# igrid_sensor.net
KiCad netlist of a schematic drawn in Altium Designer
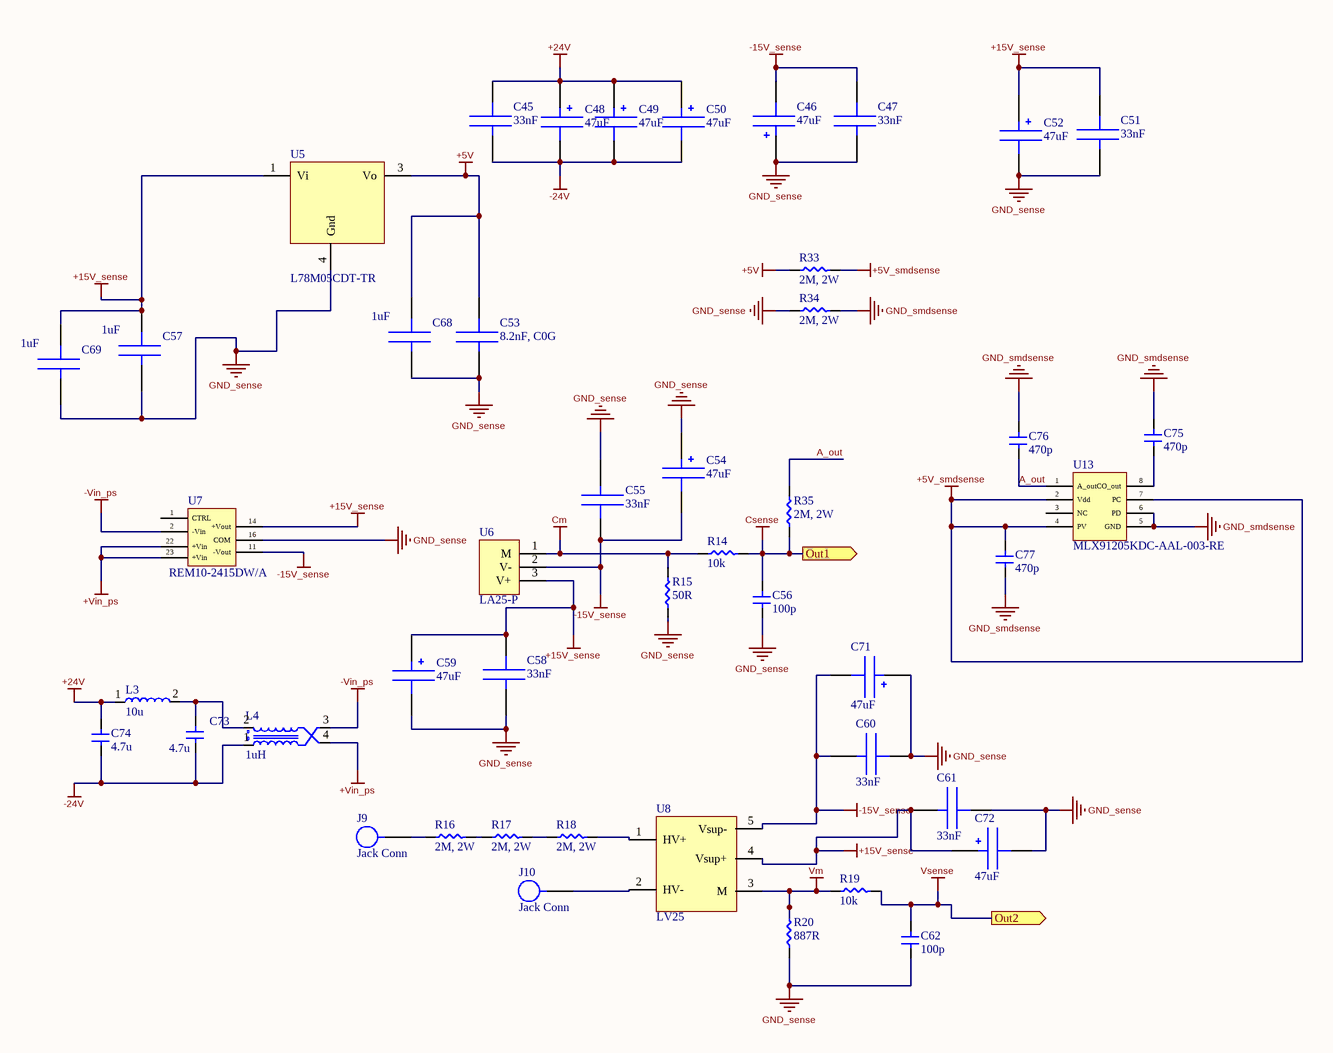
[diagram p0: igrid_sensor.SchDoc]

(export (version "E")
  (design (tool "Eeschema 10.0.6"))
  (components
    (comp (ref "C45")
      (value "33nF")
      (footprint "C1206")
      (description "Cap Ceramic 0.033uF 50V X7R 5% SMD 1206 125C Paper T/R")
      (fields
        (field (name "MANUFACTURER") "Samsung")
        (field (name "MANUFACTURER PART NUMBER") "CL31B333JBCNNNC")
      )
      (libsource (lib "power_ckt") (part "CL31B333JBCNNNC"))
    )
    (comp (ref "C46")
      (value "47uF")
      (footprint "CAPAE7266X82N")
      (description "Aluminum Electrolytic Capacitors - SMD 47uF 50V 105c")
      (fields
        (field (name "MANUFACTURER") "Nichicon")
        (field (name "MANUFACTURER PART NUMBER") "UCD1H470MCL1GS")
      )
      (libsource (lib "power_ckt") (part "UCD1H470MCL1GS"))
    )
    (comp (ref "C47")
      (value "33nF")
      (footprint "C1206")
      (description "Cap Ceramic 0.033uF 50V X7R 5% SMD 1206 125C Paper T/R")
      (fields
        (field (name "MANUFACTURER") "Samsung")
        (field (name "MANUFACTURER PART NUMBER") "CL31B333JBCNNNC")
      )
      (libsource (lib "power_ckt") (part "CL31B333JBCNNNC"))
    )
    (comp (ref "C48")
      (value "47uF")
      (footprint "CAPAE7266X82N")
      (description "Aluminum Electrolytic Capacitors - SMD 47uF 50V 105c")
      (fields
        (field (name "MANUFACTURER") "Nichicon")
        (field (name "MANUFACTURER PART NUMBER") "UCD1H470MCL1GS")
      )
      (libsource (lib "power_ckt") (part "UCD1H470MCL1GS"))
    )
    (comp (ref "C49")
      (value "47uF")
      (footprint "CAPAE7266X82N")
      (description "Aluminum Electrolytic Capacitors - SMD 47uF 50V 105c")
      (fields
        (field (name "MANUFACTURER") "Nichicon")
        (field (name "MANUFACTURER PART NUMBER") "UCD1H470MCL1GS")
      )
      (libsource (lib "power_ckt") (part "UCD1H470MCL1GS"))
    )
    (comp (ref "C50")
      (value "47uF")
      (footprint "CAPAE7266X82N")
      (description "Aluminum Electrolytic Capacitors - SMD 47uF 50V 105c")
      (fields
        (field (name "MANUFACTURER") "Nichicon")
        (field (name "MANUFACTURER PART NUMBER") "UCD1H470MCL1GS")
      )
      (libsource (lib "power_ckt") (part "UCD1H470MCL1GS"))
    )
    (comp (ref "C51")
      (value "33nF")
      (footprint "C1206")
      (description "Cap Ceramic 0.033uF 50V X7R 5% SMD 1206 125C Paper T/R")
      (fields
        (field (name "MANUFACTURER") "Samsung")
        (field (name "MANUFACTURER PART NUMBER") "CL31B333JBCNNNC")
      )
      (libsource (lib "power_ckt") (part "CL31B333JBCNNNC"))
    )
    (comp (ref "C52")
      (value "47uF")
      (footprint "CAPAE7266X82N")
      (description "Aluminum Electrolytic Capacitors - SMD 47uF 50V 105c")
      (fields
        (field (name "MANUFACTURER") "Nichicon")
        (field (name "MANUFACTURER PART NUMBER") "UCD1H470MCL1GS")
      )
      (libsource (lib "power_ckt") (part "UCD1H470MCL1GS"))
    )
    (comp (ref "C53")
      (value "8.2nF, C0G")
      (footprint "C1206")
      (description "Multilayer Ceramic Capacitors MLCC - SMD/SMT 250volts 8200pF 5% C0G AUTO")
      (fields
        (field (name "MANUFACTURER") "KEMET")
        (field (name "MANUFACTURER PART NUMBER") "C1206C822JAGACAUTO")
      )
      (libsource (lib "power_ckt") (part "C1206C822JAGACAUTO"))
    )
    (comp (ref "C54")
      (value "47uF")
      (footprint "CAPAE7266X82N")
      (description "Aluminum Electrolytic Capacitors - SMD 47uF 50V 105c")
      (fields
        (field (name "MANUFACTURER") "Nichicon")
        (field (name "MANUFACTURER PART NUMBER") "UCD1H470MCL1GS")
      )
      (libsource (lib "power_ckt") (part "UCD1H470MCL1GS"))
    )
    (comp (ref "C55")
      (value "33nF")
      (footprint "C1206")
      (description "Cap Ceramic 0.033uF 50V X7R 5% SMD 1206 125C Paper T/R")
      (fields
        (field (name "MANUFACTURER") "Samsung")
        (field (name "MANUFACTURER PART NUMBER") "CL31B333JBCNNNC")
      )
      (libsource (lib "power_ckt") (part "CL31B333JBCNNNC"))
    )
    (comp (ref "C56")
      (value "100p")
      (footprint "C0603")
      (description "Cap Ceramic 100pF 50V X7R 10% SMD 0603 125C T/R")
      (fields
        (field (name "MANUFACTURER") "Kyocera AVX")
        (field (name "MANUFACTURER PART NUMBER") "06035C101KAT2A")
      )
      (libsource (lib "voltage_sense") (part "06035C101KAT2A"))
    )
    (comp (ref "C57")
      (value "1uF")
      (footprint "C1206")
      (description "Multilayer Ceramic Capacitors MLCC - SMD/SMT 250volts 8200pF 5% C0G AUTO")
      (fields
        (field (name "MANUFACTURER") "KEMET")
        (field (name "MANUFACTURER PART NUMBER") "C1206C822JAGACAUTO")
      )
      (libsource (lib "power_ckt") (part "C1206C822JAGACAUTO"))
    )
    (comp (ref "C58")
      (value "33nF")
      (footprint "C1206")
      (description "Cap Ceramic 0.033uF 50V X7R 5% SMD 1206 125C Paper T/R")
      (fields
        (field (name "MANUFACTURER") "Samsung")
        (field (name "MANUFACTURER PART NUMBER") "CL31B333JBCNNNC")
      )
      (libsource (lib "power_ckt") (part "CL31B333JBCNNNC"))
    )
    (comp (ref "C59")
      (value "47uF")
      (footprint "CAPAE7266X82N")
      (description "Aluminum Electrolytic Capacitors - SMD 47uF 50V 105c")
      (fields
        (field (name "MANUFACTURER") "Nichicon")
        (field (name "MANUFACTURER PART NUMBER") "UCD1H470MCL1GS")
      )
      (libsource (lib "power_ckt") (part "UCD1H470MCL1GS"))
    )
    (comp (ref "C60")
      (value "33nF")
      (footprint "C1206")
      (description "Cap Ceramic 0.033uF 50V X7R 5% SMD 1206 125C Paper T/R")
      (fields
        (field (name "MANUFACTURER") "Samsung")
        (field (name "MANUFACTURER PART NUMBER") "CL31B333JBCNNNC")
      )
      (libsource (lib "power_ckt") (part "CL31B333JBCNNNC"))
    )
    (comp (ref "C61")
      (value "33nF")
      (footprint "C1206")
      (description "Cap Ceramic 0.033uF 50V X7R 5% SMD 1206 125C Paper T/R")
      (fields
        (field (name "MANUFACTURER") "Samsung")
        (field (name "MANUFACTURER PART NUMBER") "CL31B333JBCNNNC")
      )
      (libsource (lib "power_ckt") (part "CL31B333JBCNNNC"))
    )
    (comp (ref "C62")
      (value "100p")
      (footprint "C0603")
      (description "Cap Ceramic 100pF 50V X7R 10% SMD 0603 125C T/R")
      (fields
        (field (name "MANUFACTURER") "Kyocera AVX")
        (field (name "MANUFACTURER PART NUMBER") "06035C101KAT2A")
      )
      (libsource (lib "voltage_sense") (part "06035C101KAT2A"))
    )
    (comp (ref "C68")
      (value "1uF")
      (footprint "C1206")
      (description "Multilayer Ceramic Capacitors MLCC - SMD/SMT 250volts 8200pF 5% C0G AUTO")
      (fields
        (field (name "MANUFACTURER") "KEMET")
        (field (name "MANUFACTURER PART NUMBER") "C1206C822JAGACAUTO")
      )
      (libsource (lib "power_ckt") (part "C1206C822JAGACAUTO"))
    )
    (comp (ref "C69")
      (value "1uF")
      (footprint "C1206")
      (description "Multilayer Ceramic Capacitors MLCC - SMD/SMT 250volts 8200pF 5% C0G AUTO")
      (fields
        (field (name "MANUFACTURER") "KEMET")
        (field (name "MANUFACTURER PART NUMBER") "C1206C822JAGACAUTO")
      )
      (libsource (lib "power_ckt") (part "C1206C822JAGACAUTO"))
    )
    (comp (ref "C71")
      (value "47uF")
      (footprint "CAPAE7266X82N")
      (description "Aluminum Electrolytic Capacitors - SMD 47uF 50V 105c")
      (fields
        (field (name "MANUFACTURER") "Nichicon")
        (field (name "MANUFACTURER PART NUMBER") "UCD1H470MCL1GS")
      )
      (libsource (lib "power_ckt") (part "UCD1H470MCL1GS"))
    )
    (comp (ref "C72")
      (value "47uF")
      (footprint "CAPAE7266X82N")
      (description "Aluminum Electrolytic Capacitors - SMD 47uF 50V 105c")
      (fields
        (field (name "MANUFACTURER") "Nichicon")
        (field (name "MANUFACTURER PART NUMBER") "UCD1H470MCL1GS")
      )
      (libsource (lib "power_ckt") (part "UCD1H470MCL1GS"))
    )
    (comp (ref "C73")
      (value "4.7u")
      (footprint "C0805")
      (description "CAP CER 10000PF 50V C0G 0805")
      (fields
        (field (name "MANUFACTURER") "TDK")
        (field (name "MANUFACTURER PART NUMBER") "CGA4C2C0G1H103J060AA")
      )
      (libsource (lib "24_12_buck") (part "CGA4C2C0G1H103J060AA"))
    )
    (comp (ref "C74")
      (value "4.7u")
      (footprint "C0805")
      (description "CAP CER 10000PF 50V C0G 0805")
      (fields
        (field (name "MANUFACTURER") "TDK")
        (field (name "MANUFACTURER PART NUMBER") "CGA4C2C0G1H103J060AA")
      )
      (libsource (lib "24_12_buck") (part "CGA4C2C0G1H103J060AA"))
    )
    (comp (ref "C75")
      (value "470p")
      (footprint "C0603")
      (fields
        (field (name "MANUFACTURER") "Yageo")
        (field (name "MANUFACTURER PART NUMBER") "CC0603KRX7R9BB471")
        (field (name "TOLERANCE") "10%")
      )
      (libsource (lib "current_sense") (part "CC0603KRX7R9BB471"))
    )
    (comp (ref "C76")
      (value "470p")
      (footprint "C0603")
      (fields
        (field (name "MANUFACTURER") "Yageo")
        (field (name "MANUFACTURER PART NUMBER") "CC0603KRX7R9BB471")
        (field (name "TOLERANCE") "10%")
      )
      (libsource (lib "current_sense") (part "CC0603KRX7R9BB471"))
    )
    (comp (ref "C77")
      (value "470p")
      (footprint "C0603")
      (fields
        (field (name "MANUFACTURER") "Yageo")
        (field (name "MANUFACTURER PART NUMBER") "CC0603KRX7R9BB471")
        (field (name "TOLERANCE") "10%")
      )
      (libsource (lib "current_sense") (part "CC0603KRX7R9BB471"))
    )
    (comp (ref "J9")
      (value "Jack Conn")
      (footprint "575-4")
      (description "JACK NON-INSULATED .218\"")
      (fields
        (field (name "MANUFACTURER") "Keystone Electronics")
        (field (name "MANUFACTURER PART NUMBER") "575-4")
      )
      (libsource (lib "current_sense") (part "575-4"))
    )
    (comp (ref "J10")
      (value "Jack Conn")
      (footprint "575-4")
      (description "JACK NON-INSULATED .218\"")
      (fields
        (field (name "MANUFACTURER") "Keystone Electronics")
        (field (name "MANUFACTURER PART NUMBER") "575-4")
      )
      (libsource (lib "current_sense") (part "575-4"))
    )
    (comp (ref "L3")
      (value "10u")
      (footprint "SRP4020TA-100M")
      (description "Ind Power Shielded Wirewound 10uH 20% 100KHz Carbonyl Powder 1.8A T/R")
      (fields
        (field (name "MANUFACTURER") "Bourns")
        (field (name "MANUFACTURER PART NUMBER") "SRP4020TA-100M")
      )
      (libsource (lib "24_12_buck") (part "SRP4020TA-100M"))
    )
    (comp (ref "L4")
      (value "1uH")
      (footprint "744282010")
      (description "CHOKE COM MODE 2 X 1.0UH 4.75A")
      (fields
        (field (name "MANUFACTURER") "Wurth Electronics")
        (field (name "MANUFACTURER PART NUMBER") "744282010")
      )
      (libsource (lib "current_sense") (part "744282010"))
    )
    (comp (ref "R14")
      (value "10k")
      (footprint "R0603")
      (description "RES 10K OHM 1% 1/8W 0603")
      (fields
        (field (name "MANUFACTURER") "Stackpole Electronics")
        (field (name "MANUFACTURER PART NUMBER") "RNCP0603FTD10K0")
      )
      (libsource (lib "voltage_sense") (part "RNCP0603FTD10K0"))
    )
    (comp (ref "R15")
      (value "50R")
      (footprint "R0603")
      (fields
        (field (name "MANUFACTURER") "Panasonic")
        (field (name "MANUFACTURER PART NUMBER") "ERA3AEB7320V")
        (field (name "TOLERANCE") "0.1%")
      )
      (libsource (lib "24_12_buck") (part "ERA3AEB7320V"))
    )
    (comp (ref "R16")
      (value "2M, 2W")
      (footprint "R2010")
      (description "Supplied as a Tape, 2MΩ 2010 Thick Film SMD Resistor ±1% 2W - 35022M0FT")
      (fields
        (field (name "MANUFACTURER") "TE Connectivity")
        (field (name "MANUFACTURER PART NUMBER") "35022M0FT")
      )
      (libsource (lib "voltage_sense") (part "35022M0FT"))
    )
    (comp (ref "R17")
      (value "2M, 2W")
      (footprint "R2010")
      (description "Supplied as a Tape, 2MΩ 2010 Thick Film SMD Resistor ±1% 2W - 35022M0FT")
      (fields
        (field (name "MANUFACTURER") "TE Connectivity")
        (field (name "MANUFACTURER PART NUMBER") "35022M0FT")
      )
      (libsource (lib "voltage_sense") (part "35022M0FT"))
    )
    (comp (ref "R18")
      (value "2M, 2W")
      (footprint "R2010")
      (description "Supplied as a Tape, 2MΩ 2010 Thick Film SMD Resistor ±1% 2W - 35022M0FT")
      (fields
        (field (name "MANUFACTURER") "TE Connectivity")
        (field (name "MANUFACTURER PART NUMBER") "35022M0FT")
      )
      (libsource (lib "voltage_sense") (part "35022M0FT"))
    )
    (comp (ref "R19")
      (value "10k")
      (footprint "R0603")
      (description "RES 10K OHM 1% 1/8W 0603")
      (fields
        (field (name "MANUFACTURER") "Stackpole Electronics")
        (field (name "MANUFACTURER PART NUMBER") "RNCP0603FTD10K0")
      )
      (libsource (lib "voltage_sense") (part "RNCP0603FTD10K0"))
    )
    (comp (ref "R20")
      (value "887R")
      (footprint "R0603")
      (description "RES SMD 887 OHM 0.1% 1/10W 0603")
      (fields
        (field (name "MANUFACTURER") "Panasonic")
        (field (name "MANUFACTURER PART NUMBER") "ERA-3AEB8870V")
      )
      (libsource (lib "voltage_sense") (part "ERA-3AEB8870V"))
    )
    (comp (ref "R33")
      (value "2M, 2W")
      (footprint "R2010")
      (description "Supplied as a Tape, 2MΩ 2010 Thick Film SMD Resistor ±1% 2W - 35022M0FT")
      (fields
        (field (name "MANUFACTURER") "TE Connectivity")
        (field (name "MANUFACTURER PART NUMBER") "35022M0FT")
      )
      (libsource (lib "voltage_sense") (part "35022M0FT"))
    )
    (comp (ref "R34")
      (value "2M, 2W")
      (footprint "R2010")
      (description "Supplied as a Tape, 2MΩ 2010 Thick Film SMD Resistor ±1% 2W - 35022M0FT")
      (fields
        (field (name "MANUFACTURER") "TE Connectivity")
        (field (name "MANUFACTURER PART NUMBER") "35022M0FT")
      )
      (libsource (lib "voltage_sense") (part "35022M0FT"))
    )
    (comp (ref "R35")
      (value "2M, 2W")
      (footprint "R2010")
      (description "Supplied as a Tape, 2MΩ 2010 Thick Film SMD Resistor ±1% 2W - 35022M0FT")
      (fields
        (field (name "MANUFACTURER") "TE Connectivity")
        (field (name "MANUFACTURER PART NUMBER") "35022M0FT")
      )
      (libsource (lib "voltage_sense") (part "35022M0FT"))
    )
    (comp (ref "U5")
      (value "L78M05CDT-TR")
      (footprint "DPAK_LM7805")
      (description "STMICROELECTRONICS   L78M05CDT-TR   LINEAR VOLTAGE REGULATOR, 5V, DPAK-3")
      (fields (field (name "MANUFACTURER") "STMicroelectronics") (field (name "TOLERANCE") "5%"))
      (libsource (lib "24_12_buck") (part "L78M05CDT-TR"))
    )
    (comp (ref "U6")
      (value "LA25-P")
      (footprint "LA 25-P")
      (fields (field (name "MANUFACTURER") "LEM"))
      (libsource (lib "current_sense") (part "LA25-P"))
    )
    (comp (ref "U7")
      (value "REM10-2415DW/A")
      (footprint "REM10-2415DW/A")
      (description "Isolated DC/DC Converters 10W 9-36Vin +/-15Vout DIP24")
      (fields (field (name "MANUFACTURER") "Recom"))
      (libsource (lib "current_sense") (part "REM10-2415DW/A"))
    )
    (comp (ref "U8")
      (value "LV25")
      (footprint "LV25-P")
      (fields (field (name "MANUFACTURER") "LEM") (field (name "MANUFACTURER PART NUMBER") "LV25-P"))
      (libsource (lib "voltage_sense") (part "LV25-P"))
    )
    (comp (ref "U13")
      (value "MLX91205KDC-AAL-003-RE")
      (footprint "SOIC-8")
      (description "SENSOR CURRENT HALL 10MT AC/DC")
      (fields (field (name "MANUFACTURER") "Melexis"))
      (libsource (lib "current_sense") (part "MLX91205KDC-AAL-003-RE"))
    )
  )
  (nets
    (net (code "1") (name "+5V") (class "Default")
      (node (ref "C53") (pin "2") (pinfunction "2_2") (pintype "power_in"))
      (node (ref "C68") (pin "2") (pinfunction "2_2") (pintype "power_in"))
      (node (ref "R33") (pin "1") (pinfunction "3_1") (pintype "passive"))
      (node (ref "U5") (pin "3") (pinfunction "Vo_3") (pintype "passive"))
    )
    (net (code "2") (name "+5V_smdsense") (class "Default")
      (node (ref "C77") (pin "2") (pinfunction "2_2") (pintype "passive"))
      (node (ref "R33") (pin "2") (pinfunction "4_2") (pintype "passive"))
      (node (ref "U13") (pin "2") (pinfunction "Vdd_2") (pintype "power_in"))
      (node (ref "U13") (pin "4") (pinfunction "PV_4") (pintype "power_in"))
      (node (ref "U13") (pin "7") (pinfunction "PC_7") (pintype "power_in"))
    )
    (net (code "3") (name "+15V_sense") (class "Default")
      (node (ref "C51") (pin "2") (pinfunction "2_2") (pintype "power_in"))
      (node (ref "C52") (pin "1") (pinfunction "1_1") (pintype "power_in"))
      (node (ref "C57") (pin "2") (pinfunction "2_2") (pintype "power_in"))
      (node (ref "C58") (pin "2") (pinfunction "2_2") (pintype "power_in"))
      (node (ref "C59") (pin "1") (pinfunction "1_1") (pintype "power_in"))
      (node (ref "C61") (pin "1") (pinfunction "1_1") (pintype "power_in"))
      (node (ref "C69") (pin "2") (pinfunction "2_2") (pintype "power_in"))
      (node (ref "C72") (pin "1") (pinfunction "1_1") (pintype "power_in"))
      (node (ref "U5") (pin "1") (pinfunction "Vi_1") (pintype "passive"))
      (node (ref "U6") (pin "3") (pinfunction "V+_3") (pintype "power_in"))
      (node (ref "U7") (pin "14") (pinfunction "+Vout_14") (pintype "power_in"))
      (node (ref "U8") (pin "4") (pinfunction "Vsup+_4") (pintype "power_in"))
    )
    (net (code "4") (name "+24V") (class "Default")
      (node (ref "C45") (pin "2") (pinfunction "2_2") (pintype "power_in"))
      (node (ref "C48") (pin "1") (pinfunction "1_1") (pintype "power_in"))
      (node (ref "C49") (pin "1") (pinfunction "1_1") (pintype "power_in"))
      (node (ref "C50") (pin "1") (pinfunction "1_1") (pintype "power_in"))
      (node (ref "C74") (pin "2") (pinfunction "2_2") (pintype "passive"))
      (node (ref "L3") (pin "1") (pinfunction "1_1") (pintype "passive"))
    )
    (net (code "5") (name "+Vin_ps") (class "Default")
      (node (ref "L4") (pin "4") (pinfunction "4_4") (pintype "passive"))
      (node (ref "U7") (pin "22") (pinfunction "+Vin_22") (pintype "power_in"))
      (node (ref "U7") (pin "23") (pinfunction "+Vin_23") (pintype "power_in"))
    )
    (net (code "6") (name "-15V_sense") (class "Default")
      (node (ref "C46") (pin "2") (pinfunction "2_2") (pintype "power_in"))
      (node (ref "C47") (pin "2") (pinfunction "2_2") (pintype "power_in"))
      (node (ref "C54") (pin "2") (pinfunction "2_2") (pintype "power_in"))
      (node (ref "C55") (pin "2") (pinfunction "2_2") (pintype "power_in"))
      (node (ref "C60") (pin "1") (pinfunction "1_1") (pintype "power_in"))
      (node (ref "C71") (pin "2") (pinfunction "2_2") (pintype "power_in"))
      (node (ref "U6") (pin "2") (pinfunction "V-_2") (pintype "power_in"))
      (node (ref "U7") (pin "11") (pinfunction "-Vout_11") (pintype "power_in"))
      (node (ref "U8") (pin "5") (pinfunction "Vsup-_5") (pintype "power_in"))
    )
    (net (code "7") (name "-24V") (class "Default")
      (node (ref "C45") (pin "1") (pinfunction "1_1") (pintype "power_in"))
      (node (ref "C48") (pin "2") (pinfunction "2_2") (pintype "power_in"))
      (node (ref "C49") (pin "2") (pinfunction "2_2") (pintype "power_in"))
      (node (ref "C50") (pin "2") (pinfunction "2_2") (pintype "power_in"))
      (node (ref "C73") (pin "1") (pinfunction "1_1") (pintype "passive"))
      (node (ref "C74") (pin "1") (pinfunction "1_1") (pintype "passive"))
      (node (ref "L4") (pin "1") (pinfunction "1_1") (pintype "passive"))
    )
    (net (code "8") (name "-Vin_ps") (class "Default")
      (node (ref "L4") (pin "3") (pinfunction "3_3") (pintype "passive"))
      (node (ref "U7") (pin "2") (pinfunction "-Vin_2") (pintype "power_in"))
    )
    (net (code "9") (name "/A_out") (class "Default")
      (node (ref "C76") (pin "1") (pinfunction "1_1") (pintype "passive"))
      (node (ref "R35") (pin "2") (pinfunction "4_2") (pintype "passive"))
      (node (ref "U13") (pin "1") (pinfunction "A_out_1") (pintype "power_in"))
    )
    (net (code "10") (name "Cm") (class "Default")
      (node (ref "R14") (pin "1") (pinfunction "3_1") (pintype "passive"))
      (node (ref "R15") (pin "2") (pinfunction "4_2") (pintype "passive"))
      (node (ref "U6") (pin "1") (pinfunction "M_1") (pintype "power_in"))
    )
    (net (code "11") (name "Csense") (class "Default")
      (node (ref "C56") (pin "2") (pinfunction "2_2") (pintype "passive"))
      (node (ref "R14") (pin "2") (pinfunction "4_2") (pintype "passive"))
      (node (ref "R35") (pin "1") (pinfunction "3_1") (pintype "passive"))
    )
    (net (code "12") (name "GND_sense") (class "Default")
      (node (ref "C46") (pin "1") (pinfunction "1_1") (pintype "power_in"))
      (node (ref "C47") (pin "1") (pinfunction "1_1") (pintype "power_in"))
      (node (ref "C51") (pin "1") (pinfunction "1_1") (pintype "power_in"))
      (node (ref "C52") (pin "2") (pinfunction "2_2") (pintype "power_in"))
      (node (ref "C53") (pin "1") (pinfunction "1_1") (pintype "power_in"))
      (node (ref "C54") (pin "1") (pinfunction "1_1") (pintype "power_in"))
      (node (ref "C55") (pin "1") (pinfunction "1_1") (pintype "power_in"))
      (node (ref "C56") (pin "1") (pinfunction "1_1") (pintype "passive"))
      (node (ref "C57") (pin "1") (pinfunction "1_1") (pintype "power_in"))
      (node (ref "C58") (pin "1") (pinfunction "1_1") (pintype "power_in"))
      (node (ref "C59") (pin "2") (pinfunction "2_2") (pintype "power_in"))
      (node (ref "C60") (pin "2") (pinfunction "2_2") (pintype "power_in"))
      (node (ref "C61") (pin "2") (pinfunction "2_2") (pintype "power_in"))
      (node (ref "C62") (pin "1") (pinfunction "1_1") (pintype "passive"))
      (node (ref "C68") (pin "1") (pinfunction "1_1") (pintype "power_in"))
      (node (ref "C69") (pin "1") (pinfunction "1_1") (pintype "power_in"))
      (node (ref "C71") (pin "1") (pinfunction "1_1") (pintype "power_in"))
      (node (ref "C72") (pin "2") (pinfunction "2_2") (pintype "power_in"))
      (node (ref "R15") (pin "1") (pinfunction "3_1") (pintype "passive"))
      (node (ref "R20") (pin "1") (pinfunction "3_1") (pintype "passive"))
      (node (ref "R34") (pin "1") (pinfunction "3_1") (pintype "passive"))
      (node (ref "U5") (pin "4") (pinfunction "Gnd_4") (pintype "passive"))
      (node (ref "U7") (pin "16") (pinfunction "COM_16") (pintype "power_in"))
    )
    (net (code "13") (name "GND_smdsense") (class "Default")
      (node (ref "C75") (pin "2") (pinfunction "2_2") (pintype "passive"))
      (node (ref "C76") (pin "2") (pinfunction "2_2") (pintype "passive"))
      (node (ref "C77") (pin "1") (pinfunction "1_1") (pintype "passive"))
      (node (ref "R34") (pin "2") (pinfunction "4_2") (pintype "passive"))
      (node (ref "U13") (pin "5") (pinfunction "GND_5") (pintype "power_in"))
      (node (ref "U13") (pin "6") (pinfunction "PD_6") (pintype "power_in"))
    )
    (net (code "14") (name "Net-(C73-Pad2)") (class "Default")
      (node (ref "C73") (pin "2") (pinfunction "2_2") (pintype "passive"))
      (node (ref "L3") (pin "2") (pinfunction "2_2") (pintype "passive"))
      (node (ref "L4") (pin "2") (pinfunction "2_2") (pintype "passive"))
    )
    (net (code "15") (name "Net-(R16-3)") (class "Default")
      (node (ref "J9") (pin "1") (pinfunction "1_1") (pintype "power_in"))
      (node (ref "R16") (pin "1") (pinfunction "3_1") (pintype "passive"))
    )
    (net (code "16") (name "Net-(R16-4)") (class "Default")
      (node (ref "R16") (pin "2") (pinfunction "4_2") (pintype "passive"))
      (node (ref "R17") (pin "1") (pinfunction "3_1") (pintype "passive"))
    )
    (net (code "17") (name "Net-(R17-4)") (class "Default")
      (node (ref "R17") (pin "2") (pinfunction "4_2") (pintype "passive"))
      (node (ref "R18") (pin "1") (pinfunction "3_1") (pintype "passive"))
    )
    (net (code "18") (name "Net-(R18-4)") (class "Default")
      (node (ref "R18") (pin "2") (pinfunction "4_2") (pintype "passive"))
      (node (ref "U8") (pin "1") (pinfunction "HV+_1") (pintype "power_in"))
    )
    (net (code "19") (name "Net-(U8-HV-)") (class "Default")
      (node (ref "J10") (pin "1") (pinfunction "1_1") (pintype "power_in"))
      (node (ref "U8") (pin "2") (pinfunction "HV-_2") (pintype "power_in"))
    )
    (net (code "20") (name "Net-(U13-CO_out)") (class "Default")
      (node (ref "C75") (pin "1") (pinfunction "1_1") (pintype "passive"))
      (node (ref "U13") (pin "8") (pinfunction "CO_out_8") (pintype "power_in"))
    )
    (net (code "21") (name "Vm") (class "Default")
      (node (ref "R19") (pin "1") (pinfunction "3_1") (pintype "passive"))
      (node (ref "R20") (pin "2") (pinfunction "4_2") (pintype "passive"))
      (node (ref "U8") (pin "3") (pinfunction "M_3") (pintype "power_in"))
    )
    (net (code "22") (name "Vsense") (class "Default")
      (node (ref "C62") (pin "2") (pinfunction "2_2") (pintype "passive"))
      (node (ref "R19") (pin "2") (pinfunction "4_2") (pintype "passive"))
    )
    (net (code "23") (name "unconnected-(U7-CTRL-Pad1)") (class "Default")
      (node (ref "U7") (pin "1") (pinfunction "CTRL_1") (pintype "power_in"))
    )
    (net (code "24") (name "unconnected-(U13-NC-Pad3)") (class "Default")
      (node (ref "U13") (pin "3") (pinfunction "NC_3") (pintype "power_in"))
    )
  )
)
